# DR_EIB-128_expandedv1_3.net
KiCad netlist of a schematic drawn in EAGLE
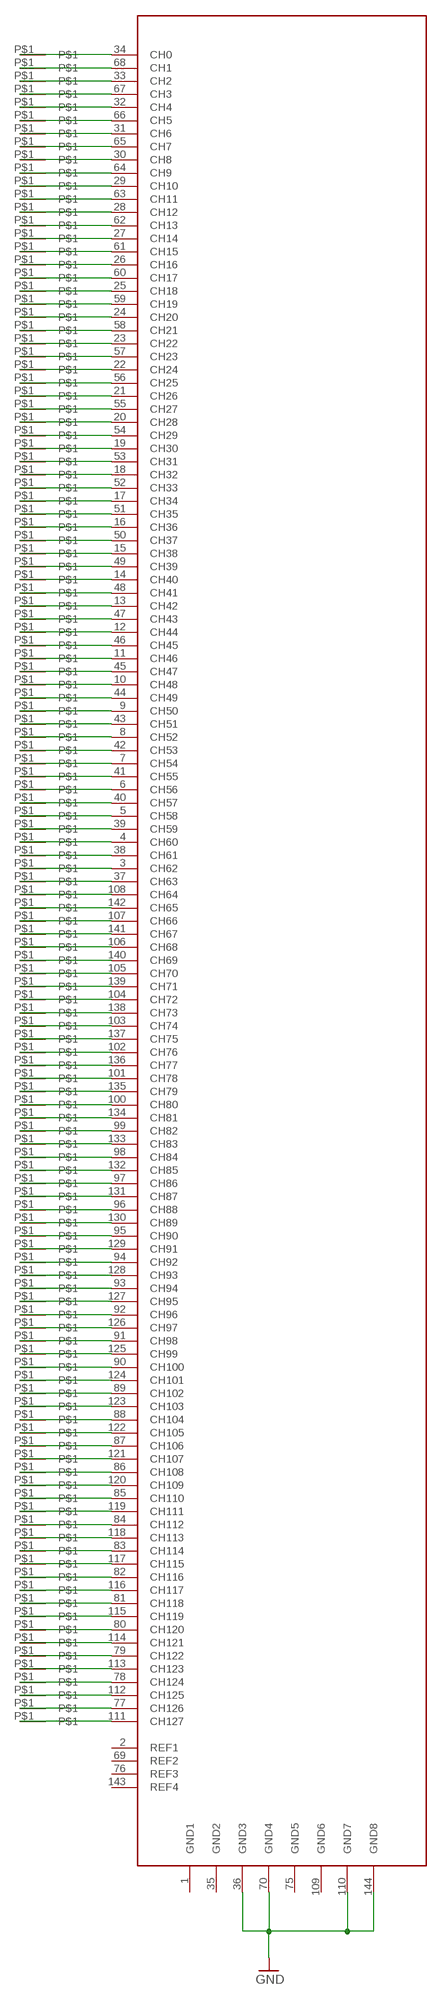
[diagram p0: schematic, sheet 1]

(export (version "E")
  (design (tool "Eeschema 10.0.6"))
  (components
    (comp (ref "H$0")
      (value "TARRAYSHUTTLEHOLE")
      (footprint "eagle-import:TARRAYSHUTTLEHOLE")
      (libsource (lib "eagle-import") (part "TARRAYSHUTTLEHOLE"))
    )
    (comp (ref "H$1")
      (value "TARRAYSHUTTLEHOLE")
      (footprint "eagle-import:TARRAYSHUTTLEHOLE")
      (libsource (lib "eagle-import") (part "TARRAYSHUTTLEHOLE"))
    )
    (comp (ref "H$2")
      (value "TARRAYSHUTTLEHOLE")
      (footprint "eagle-import:TARRAYSHUTTLEHOLE")
      (libsource (lib "eagle-import") (part "TARRAYSHUTTLEHOLE"))
    )
    (comp (ref "H$3")
      (value "TARRAYSHUTTLEHOLE")
      (footprint "eagle-import:TARRAYSHUTTLEHOLE")
      (libsource (lib "eagle-import") (part "TARRAYSHUTTLEHOLE"))
    )
    (comp (ref "H$4")
      (value "TARRAYSHUTTLEHOLE")
      (footprint "eagle-import:TARRAYSHUTTLEHOLE")
      (libsource (lib "eagle-import") (part "TARRAYSHUTTLEHOLE"))
    )
    (comp (ref "H$5")
      (value "TARRAYSHUTTLEHOLE")
      (footprint "eagle-import:TARRAYSHUTTLEHOLE")
      (libsource (lib "eagle-import") (part "TARRAYSHUTTLEHOLE"))
    )
    (comp (ref "H$6")
      (value "TARRAYSHUTTLEHOLE")
      (footprint "eagle-import:TARRAYSHUTTLEHOLE")
      (libsource (lib "eagle-import") (part "TARRAYSHUTTLEHOLE"))
    )
    (comp (ref "H$7")
      (value "TARRAYSHUTTLEHOLE")
      (footprint "eagle-import:TARRAYSHUTTLEHOLE")
      (libsource (lib "eagle-import") (part "TARRAYSHUTTLEHOLE"))
    )
    (comp (ref "H$8")
      (value "TARRAYSHUTTLEHOLE")
      (footprint "eagle-import:TARRAYSHUTTLEHOLE")
      (libsource (lib "eagle-import") (part "TARRAYSHUTTLEHOLE"))
    )
    (comp (ref "H$9")
      (value "TARRAYSHUTTLEHOLE")
      (footprint "eagle-import:TARRAYSHUTTLEHOLE")
      (libsource (lib "eagle-import") (part "TARRAYSHUTTLEHOLE"))
    )
    (comp (ref "H$10")
      (value "TARRAYSHUTTLEHOLE")
      (footprint "eagle-import:TARRAYSHUTTLEHOLE")
      (libsource (lib "eagle-import") (part "TARRAYSHUTTLEHOLE"))
    )
    (comp (ref "H$11")
      (value "TARRAYSHUTTLEHOLE")
      (footprint "eagle-import:TARRAYSHUTTLEHOLE")
      (libsource (lib "eagle-import") (part "TARRAYSHUTTLEHOLE"))
    )
    (comp (ref "H$12")
      (value "TARRAYSHUTTLEHOLE")
      (footprint "eagle-import:TARRAYSHUTTLEHOLE")
      (libsource (lib "eagle-import") (part "TARRAYSHUTTLEHOLE"))
    )
    (comp (ref "H$13")
      (value "TARRAYSHUTTLEHOLE")
      (footprint "eagle-import:TARRAYSHUTTLEHOLE")
      (libsource (lib "eagle-import") (part "TARRAYSHUTTLEHOLE"))
    )
    (comp (ref "H$14")
      (value "TARRAYSHUTTLEHOLE")
      (footprint "eagle-import:TARRAYSHUTTLEHOLE")
      (libsource (lib "eagle-import") (part "TARRAYSHUTTLEHOLE"))
    )
    (comp (ref "H$15")
      (value "TARRAYSHUTTLEHOLE")
      (footprint "eagle-import:TARRAYSHUTTLEHOLE")
      (libsource (lib "eagle-import") (part "TARRAYSHUTTLEHOLE"))
    )
    (comp (ref "H$16")
      (value "TARRAYSHUTTLEHOLE")
      (footprint "eagle-import:TARRAYSHUTTLEHOLE")
      (libsource (lib "eagle-import") (part "TARRAYSHUTTLEHOLE"))
    )
    (comp (ref "H$17")
      (value "TARRAYSHUTTLEHOLE")
      (footprint "eagle-import:TARRAYSHUTTLEHOLE")
      (libsource (lib "eagle-import") (part "TARRAYSHUTTLEHOLE"))
    )
    (comp (ref "H$18")
      (value "TARRAYSHUTTLEHOLE")
      (footprint "eagle-import:TARRAYSHUTTLEHOLE")
      (libsource (lib "eagle-import") (part "TARRAYSHUTTLEHOLE"))
    )
    (comp (ref "H$19")
      (value "TARRAYSHUTTLEHOLE")
      (footprint "eagle-import:TARRAYSHUTTLEHOLE")
      (libsource (lib "eagle-import") (part "TARRAYSHUTTLEHOLE"))
    )
    (comp (ref "H$20")
      (value "TARRAYSHUTTLEHOLE")
      (footprint "eagle-import:TARRAYSHUTTLEHOLE")
      (libsource (lib "eagle-import") (part "TARRAYSHUTTLEHOLE"))
    )
    (comp (ref "H$21")
      (value "TARRAYSHUTTLEHOLE")
      (footprint "eagle-import:TARRAYSHUTTLEHOLE")
      (libsource (lib "eagle-import") (part "TARRAYSHUTTLEHOLE"))
    )
    (comp (ref "H$22")
      (value "TARRAYSHUTTLEHOLE")
      (footprint "eagle-import:TARRAYSHUTTLEHOLE")
      (libsource (lib "eagle-import") (part "TARRAYSHUTTLEHOLE"))
    )
    (comp (ref "H$23")
      (value "TARRAYSHUTTLEHOLE")
      (footprint "eagle-import:TARRAYSHUTTLEHOLE")
      (libsource (lib "eagle-import") (part "TARRAYSHUTTLEHOLE"))
    )
    (comp (ref "H$24")
      (value "TARRAYSHUTTLEHOLE")
      (footprint "eagle-import:TARRAYSHUTTLEHOLE")
      (libsource (lib "eagle-import") (part "TARRAYSHUTTLEHOLE"))
    )
    (comp (ref "H$25")
      (value "TARRAYSHUTTLEHOLE")
      (footprint "eagle-import:TARRAYSHUTTLEHOLE")
      (libsource (lib "eagle-import") (part "TARRAYSHUTTLEHOLE"))
    )
    (comp (ref "H$26")
      (value "TARRAYSHUTTLEHOLE")
      (footprint "eagle-import:TARRAYSHUTTLEHOLE")
      (libsource (lib "eagle-import") (part "TARRAYSHUTTLEHOLE"))
    )
    (comp (ref "H$27")
      (value "TARRAYSHUTTLEHOLE")
      (footprint "eagle-import:TARRAYSHUTTLEHOLE")
      (libsource (lib "eagle-import") (part "TARRAYSHUTTLEHOLE"))
    )
    (comp (ref "H$28")
      (value "TARRAYSHUTTLEHOLE")
      (footprint "eagle-import:TARRAYSHUTTLEHOLE")
      (libsource (lib "eagle-import") (part "TARRAYSHUTTLEHOLE"))
    )
    (comp (ref "H$29")
      (value "TARRAYSHUTTLEHOLE")
      (footprint "eagle-import:TARRAYSHUTTLEHOLE")
      (libsource (lib "eagle-import") (part "TARRAYSHUTTLEHOLE"))
    )
    (comp (ref "H$30")
      (value "TARRAYSHUTTLEHOLE")
      (footprint "eagle-import:TARRAYSHUTTLEHOLE")
      (libsource (lib "eagle-import") (part "TARRAYSHUTTLEHOLE"))
    )
    (comp (ref "H$31")
      (value "TARRAYSHUTTLEHOLE")
      (footprint "eagle-import:TARRAYSHUTTLEHOLE")
      (libsource (lib "eagle-import") (part "TARRAYSHUTTLEHOLE"))
    )
    (comp (ref "H$32")
      (value "TARRAYSHUTTLEHOLE")
      (footprint "eagle-import:TARRAYSHUTTLEHOLE")
      (libsource (lib "eagle-import") (part "TARRAYSHUTTLEHOLE"))
    )
    (comp (ref "H$33")
      (value "TARRAYSHUTTLEHOLE")
      (footprint "eagle-import:TARRAYSHUTTLEHOLE")
      (libsource (lib "eagle-import") (part "TARRAYSHUTTLEHOLE"))
    )
    (comp (ref "H$34")
      (value "TARRAYSHUTTLEHOLE")
      (footprint "eagle-import:TARRAYSHUTTLEHOLE")
      (libsource (lib "eagle-import") (part "TARRAYSHUTTLEHOLE"))
    )
    (comp (ref "H$35")
      (value "TARRAYSHUTTLEHOLE")
      (footprint "eagle-import:TARRAYSHUTTLEHOLE")
      (libsource (lib "eagle-import") (part "TARRAYSHUTTLEHOLE"))
    )
    (comp (ref "H$36")
      (value "TARRAYSHUTTLEHOLE")
      (footprint "eagle-import:TARRAYSHUTTLEHOLE")
      (libsource (lib "eagle-import") (part "TARRAYSHUTTLEHOLE"))
    )
    (comp (ref "H$37")
      (value "TARRAYSHUTTLEHOLE")
      (footprint "eagle-import:TARRAYSHUTTLEHOLE")
      (libsource (lib "eagle-import") (part "TARRAYSHUTTLEHOLE"))
    )
    (comp (ref "H$38")
      (value "TARRAYSHUTTLEHOLE")
      (footprint "eagle-import:TARRAYSHUTTLEHOLE")
      (libsource (lib "eagle-import") (part "TARRAYSHUTTLEHOLE"))
    )
    (comp (ref "H$39")
      (value "TARRAYSHUTTLEHOLE")
      (footprint "eagle-import:TARRAYSHUTTLEHOLE")
      (libsource (lib "eagle-import") (part "TARRAYSHUTTLEHOLE"))
    )
    (comp (ref "H$40")
      (value "TARRAYSHUTTLEHOLE")
      (footprint "eagle-import:TARRAYSHUTTLEHOLE")
      (libsource (lib "eagle-import") (part "TARRAYSHUTTLEHOLE"))
    )
    (comp (ref "H$41")
      (value "TARRAYSHUTTLEHOLE")
      (footprint "eagle-import:TARRAYSHUTTLEHOLE")
      (libsource (lib "eagle-import") (part "TARRAYSHUTTLEHOLE"))
    )
    (comp (ref "H$42")
      (value "TARRAYSHUTTLEHOLE")
      (footprint "eagle-import:TARRAYSHUTTLEHOLE")
      (libsource (lib "eagle-import") (part "TARRAYSHUTTLEHOLE"))
    )
    (comp (ref "H$43")
      (value "TARRAYSHUTTLEHOLE")
      (footprint "eagle-import:TARRAYSHUTTLEHOLE")
      (libsource (lib "eagle-import") (part "TARRAYSHUTTLEHOLE"))
    )
    (comp (ref "H$44")
      (value "TARRAYSHUTTLEHOLE")
      (footprint "eagle-import:TARRAYSHUTTLEHOLE")
      (libsource (lib "eagle-import") (part "TARRAYSHUTTLEHOLE"))
    )
    (comp (ref "H$45")
      (value "TARRAYSHUTTLEHOLE")
      (footprint "eagle-import:TARRAYSHUTTLEHOLE")
      (libsource (lib "eagle-import") (part "TARRAYSHUTTLEHOLE"))
    )
    (comp (ref "H$46")
      (value "TARRAYSHUTTLEHOLE")
      (footprint "eagle-import:TARRAYSHUTTLEHOLE")
      (libsource (lib "eagle-import") (part "TARRAYSHUTTLEHOLE"))
    )
    (comp (ref "H$47")
      (value "TARRAYSHUTTLEHOLE")
      (footprint "eagle-import:TARRAYSHUTTLEHOLE")
      (libsource (lib "eagle-import") (part "TARRAYSHUTTLEHOLE"))
    )
    (comp (ref "H$48")
      (value "TARRAYSHUTTLEHOLE")
      (footprint "eagle-import:TARRAYSHUTTLEHOLE")
      (libsource (lib "eagle-import") (part "TARRAYSHUTTLEHOLE"))
    )
    (comp (ref "H$49")
      (value "TARRAYSHUTTLEHOLE")
      (footprint "eagle-import:TARRAYSHUTTLEHOLE")
      (libsource (lib "eagle-import") (part "TARRAYSHUTTLEHOLE"))
    )
    (comp (ref "H$50")
      (value "TARRAYSHUTTLEHOLE")
      (footprint "eagle-import:TARRAYSHUTTLEHOLE")
      (libsource (lib "eagle-import") (part "TARRAYSHUTTLEHOLE"))
    )
    (comp (ref "H$51")
      (value "TARRAYSHUTTLEHOLE")
      (footprint "eagle-import:TARRAYSHUTTLEHOLE")
      (libsource (lib "eagle-import") (part "TARRAYSHUTTLEHOLE"))
    )
    (comp (ref "H$52")
      (value "TARRAYSHUTTLEHOLE")
      (footprint "eagle-import:TARRAYSHUTTLEHOLE")
      (libsource (lib "eagle-import") (part "TARRAYSHUTTLEHOLE"))
    )
    (comp (ref "H$53")
      (value "TARRAYSHUTTLEHOLE")
      (footprint "eagle-import:TARRAYSHUTTLEHOLE")
      (libsource (lib "eagle-import") (part "TARRAYSHUTTLEHOLE"))
    )
    (comp (ref "H$54")
      (value "TARRAYSHUTTLEHOLE")
      (footprint "eagle-import:TARRAYSHUTTLEHOLE")
      (libsource (lib "eagle-import") (part "TARRAYSHUTTLEHOLE"))
    )
    (comp (ref "H$55")
      (value "TARRAYSHUTTLEHOLE")
      (footprint "eagle-import:TARRAYSHUTTLEHOLE")
      (libsource (lib "eagle-import") (part "TARRAYSHUTTLEHOLE"))
    )
    (comp (ref "H$56")
      (value "TARRAYSHUTTLEHOLE")
      (footprint "eagle-import:TARRAYSHUTTLEHOLE")
      (libsource (lib "eagle-import") (part "TARRAYSHUTTLEHOLE"))
    )
    (comp (ref "H$57")
      (value "TARRAYSHUTTLEHOLE")
      (footprint "eagle-import:TARRAYSHUTTLEHOLE")
      (libsource (lib "eagle-import") (part "TARRAYSHUTTLEHOLE"))
    )
    (comp (ref "H$58")
      (value "TARRAYSHUTTLEHOLE")
      (footprint "eagle-import:TARRAYSHUTTLEHOLE")
      (libsource (lib "eagle-import") (part "TARRAYSHUTTLEHOLE"))
    )
    (comp (ref "H$59")
      (value "TARRAYSHUTTLEHOLE")
      (footprint "eagle-import:TARRAYSHUTTLEHOLE")
      (libsource (lib "eagle-import") (part "TARRAYSHUTTLEHOLE"))
    )
    (comp (ref "H$60")
      (value "TARRAYSHUTTLEHOLE")
      (footprint "eagle-import:TARRAYSHUTTLEHOLE")
      (libsource (lib "eagle-import") (part "TARRAYSHUTTLEHOLE"))
    )
    (comp (ref "H$61")
      (value "TARRAYSHUTTLEHOLE")
      (footprint "eagle-import:TARRAYSHUTTLEHOLE")
      (libsource (lib "eagle-import") (part "TARRAYSHUTTLEHOLE"))
    )
    (comp (ref "H$62")
      (value "TARRAYSHUTTLEHOLE")
      (footprint "eagle-import:TARRAYSHUTTLEHOLE")
      (libsource (lib "eagle-import") (part "TARRAYSHUTTLEHOLE"))
    )
    (comp (ref "H$63")
      (value "TARRAYSHUTTLEHOLE")
      (footprint "eagle-import:TARRAYSHUTTLEHOLE")
      (libsource (lib "eagle-import") (part "TARRAYSHUTTLEHOLE"))
    )
    (comp (ref "H$64")
      (value "TARRAYSHUTTLEHOLE")
      (footprint "eagle-import:TARRAYSHUTTLEHOLE")
      (libsource (lib "eagle-import") (part "TARRAYSHUTTLEHOLE"))
    )
    (comp (ref "H$65")
      (value "TARRAYSHUTTLEHOLE")
      (footprint "eagle-import:TARRAYSHUTTLEHOLE")
      (libsource (lib "eagle-import") (part "TARRAYSHUTTLEHOLE"))
    )
    (comp (ref "H$66")
      (value "TARRAYSHUTTLEHOLE")
      (footprint "eagle-import:TARRAYSHUTTLEHOLE")
      (libsource (lib "eagle-import") (part "TARRAYSHUTTLEHOLE"))
    )
    (comp (ref "H$67")
      (value "TARRAYSHUTTLEHOLE")
      (footprint "eagle-import:TARRAYSHUTTLEHOLE")
      (libsource (lib "eagle-import") (part "TARRAYSHUTTLEHOLE"))
    )
    (comp (ref "H$68")
      (value "TARRAYSHUTTLEHOLE")
      (footprint "eagle-import:TARRAYSHUTTLEHOLE")
      (libsource (lib "eagle-import") (part "TARRAYSHUTTLEHOLE"))
    )
    (comp (ref "H$69")
      (value "TARRAYSHUTTLEHOLE")
      (footprint "eagle-import:TARRAYSHUTTLEHOLE")
      (libsource (lib "eagle-import") (part "TARRAYSHUTTLEHOLE"))
    )
    (comp (ref "H$70")
      (value "TARRAYSHUTTLEHOLE")
      (footprint "eagle-import:TARRAYSHUTTLEHOLE")
      (libsource (lib "eagle-import") (part "TARRAYSHUTTLEHOLE"))
    )
    (comp (ref "H$71")
      (value "TARRAYSHUTTLEHOLE")
      (footprint "eagle-import:TARRAYSHUTTLEHOLE")
      (libsource (lib "eagle-import") (part "TARRAYSHUTTLEHOLE"))
    )
    (comp (ref "H$72")
      (value "TARRAYSHUTTLEHOLE")
      (footprint "eagle-import:TARRAYSHUTTLEHOLE")
      (libsource (lib "eagle-import") (part "TARRAYSHUTTLEHOLE"))
    )
    (comp (ref "H$73")
      (value "TARRAYSHUTTLEHOLE")
      (footprint "eagle-import:TARRAYSHUTTLEHOLE")
      (libsource (lib "eagle-import") (part "TARRAYSHUTTLEHOLE"))
    )
    (comp (ref "H$74")
      (value "TARRAYSHUTTLEHOLE")
      (footprint "eagle-import:TARRAYSHUTTLEHOLE")
      (libsource (lib "eagle-import") (part "TARRAYSHUTTLEHOLE"))
    )
    (comp (ref "H$75")
      (value "TARRAYSHUTTLEHOLE")
      (footprint "eagle-import:TARRAYSHUTTLEHOLE")
      (libsource (lib "eagle-import") (part "TARRAYSHUTTLEHOLE"))
    )
    (comp (ref "H$76")
      (value "TARRAYSHUTTLEHOLE")
      (footprint "eagle-import:TARRAYSHUTTLEHOLE")
      (libsource (lib "eagle-import") (part "TARRAYSHUTTLEHOLE"))
    )
    (comp (ref "H$77")
      (value "TARRAYSHUTTLEHOLE")
      (footprint "eagle-import:TARRAYSHUTTLEHOLE")
      (libsource (lib "eagle-import") (part "TARRAYSHUTTLEHOLE"))
    )
    (comp (ref "H$78")
      (value "TARRAYSHUTTLEHOLE")
      (footprint "eagle-import:TARRAYSHUTTLEHOLE")
      (libsource (lib "eagle-import") (part "TARRAYSHUTTLEHOLE"))
    )
    (comp (ref "H$79")
      (value "TARRAYSHUTTLEHOLE")
      (footprint "eagle-import:TARRAYSHUTTLEHOLE")
      (libsource (lib "eagle-import") (part "TARRAYSHUTTLEHOLE"))
    )
    (comp (ref "H$80")
      (value "TARRAYSHUTTLEHOLE")
      (footprint "eagle-import:TARRAYSHUTTLEHOLE")
      (libsource (lib "eagle-import") (part "TARRAYSHUTTLEHOLE"))
    )
    (comp (ref "H$81")
      (value "TARRAYSHUTTLEHOLE")
      (footprint "eagle-import:TARRAYSHUTTLEHOLE")
      (libsource (lib "eagle-import") (part "TARRAYSHUTTLEHOLE"))
    )
    (comp (ref "H$82")
      (value "TARRAYSHUTTLEHOLE")
      (footprint "eagle-import:TARRAYSHUTTLEHOLE")
      (libsource (lib "eagle-import") (part "TARRAYSHUTTLEHOLE"))
    )
    (comp (ref "H$83")
      (value "TARRAYSHUTTLEHOLE")
      (footprint "eagle-import:TARRAYSHUTTLEHOLE")
      (libsource (lib "eagle-import") (part "TARRAYSHUTTLEHOLE"))
    )
    (comp (ref "H$84")
      (value "TARRAYSHUTTLEHOLE")
      (footprint "eagle-import:TARRAYSHUTTLEHOLE")
      (libsource (lib "eagle-import") (part "TARRAYSHUTTLEHOLE"))
    )
    (comp (ref "H$85")
      (value "TARRAYSHUTTLEHOLE")
      (footprint "eagle-import:TARRAYSHUTTLEHOLE")
      (libsource (lib "eagle-import") (part "TARRAYSHUTTLEHOLE"))
    )
    (comp (ref "H$86")
      (value "TARRAYSHUTTLEHOLE")
      (footprint "eagle-import:TARRAYSHUTTLEHOLE")
      (libsource (lib "eagle-import") (part "TARRAYSHUTTLEHOLE"))
    )
    (comp (ref "H$87")
      (value "TARRAYSHUTTLEHOLE")
      (footprint "eagle-import:TARRAYSHUTTLEHOLE")
      (libsource (lib "eagle-import") (part "TARRAYSHUTTLEHOLE"))
    )
    (comp (ref "H$88")
      (value "TARRAYSHUTTLEHOLE")
      (footprint "eagle-import:TARRAYSHUTTLEHOLE")
      (libsource (lib "eagle-import") (part "TARRAYSHUTTLEHOLE"))
    )
    (comp (ref "H$89")
      (value "TARRAYSHUTTLEHOLE")
      (footprint "eagle-import:TARRAYSHUTTLEHOLE")
      (libsource (lib "eagle-import") (part "TARRAYSHUTTLEHOLE"))
    )
    (comp (ref "H$90")
      (value "TARRAYSHUTTLEHOLE")
      (footprint "eagle-import:TARRAYSHUTTLEHOLE")
      (libsource (lib "eagle-import") (part "TARRAYSHUTTLEHOLE"))
    )
    (comp (ref "H$91")
      (value "TARRAYSHUTTLEHOLE")
      (footprint "eagle-import:TARRAYSHUTTLEHOLE")
      (libsource (lib "eagle-import") (part "TARRAYSHUTTLEHOLE"))
    )
    (comp (ref "H$92")
      (value "TARRAYSHUTTLEHOLE")
      (footprint "eagle-import:TARRAYSHUTTLEHOLE")
      (libsource (lib "eagle-import") (part "TARRAYSHUTTLEHOLE"))
    )
    (comp (ref "H$93")
      (value "TARRAYSHUTTLEHOLE")
      (footprint "eagle-import:TARRAYSHUTTLEHOLE")
      (libsource (lib "eagle-import") (part "TARRAYSHUTTLEHOLE"))
    )
    (comp (ref "H$94")
      (value "TARRAYSHUTTLEHOLE")
      (footprint "eagle-import:TARRAYSHUTTLEHOLE")
      (libsource (lib "eagle-import") (part "TARRAYSHUTTLEHOLE"))
    )
    (comp (ref "H$95")
      (value "TARRAYSHUTTLEHOLE")
      (footprint "eagle-import:TARRAYSHUTTLEHOLE")
      (libsource (lib "eagle-import") (part "TARRAYSHUTTLEHOLE"))
    )
    (comp (ref "H$96")
      (value "TARRAYSHUTTLEHOLE")
      (footprint "eagle-import:TARRAYSHUTTLEHOLE")
      (libsource (lib "eagle-import") (part "TARRAYSHUTTLEHOLE"))
    )
    (comp (ref "H$97")
      (value "TARRAYSHUTTLEHOLE")
      (footprint "eagle-import:TARRAYSHUTTLEHOLE")
      (libsource (lib "eagle-import") (part "TARRAYSHUTTLEHOLE"))
    )
    (comp (ref "H$98")
      (value "TARRAYSHUTTLEHOLE")
      (footprint "eagle-import:TARRAYSHUTTLEHOLE")
      (libsource (lib "eagle-import") (part "TARRAYSHUTTLEHOLE"))
    )
    (comp (ref "H$99")
      (value "TARRAYSHUTTLEHOLE")
      (footprint "eagle-import:TARRAYSHUTTLEHOLE")
      (libsource (lib "eagle-import") (part "TARRAYSHUTTLEHOLE"))
    )
    (comp (ref "H$100")
      (value "TARRAYSHUTTLEHOLE")
      (footprint "eagle-import:TARRAYSHUTTLEHOLE")
      (libsource (lib "eagle-import") (part "TARRAYSHUTTLEHOLE"))
    )
    (comp (ref "H$101")
      (value "TARRAYSHUTTLEHOLE")
      (footprint "eagle-import:TARRAYSHUTTLEHOLE")
      (libsource (lib "eagle-import") (part "TARRAYSHUTTLEHOLE"))
    )
    (comp (ref "H$102")
      (value "TARRAYSHUTTLEHOLE")
      (footprint "eagle-import:TARRAYSHUTTLEHOLE")
      (libsource (lib "eagle-import") (part "TARRAYSHUTTLEHOLE"))
    )
    (comp (ref "H$103")
      (value "TARRAYSHUTTLEHOLE")
      (footprint "eagle-import:TARRAYSHUTTLEHOLE")
      (libsource (lib "eagle-import") (part "TARRAYSHUTTLEHOLE"))
    )
    (comp (ref "H$104")
      (value "TARRAYSHUTTLEHOLE")
      (footprint "eagle-import:TARRAYSHUTTLEHOLE")
      (libsource (lib "eagle-import") (part "TARRAYSHUTTLEHOLE"))
    )
    (comp (ref "H$105")
      (value "TARRAYSHUTTLEHOLE")
      (footprint "eagle-import:TARRAYSHUTTLEHOLE")
      (libsource (lib "eagle-import") (part "TARRAYSHUTTLEHOLE"))
    )
    (comp (ref "H$106")
      (value "TARRAYSHUTTLEHOLE")
      (footprint "eagle-import:TARRAYSHUTTLEHOLE")
      (libsource (lib "eagle-import") (part "TARRAYSHUTTLEHOLE"))
    )
    (comp (ref "H$107")
      (value "TARRAYSHUTTLEHOLE")
      (footprint "eagle-import:TARRAYSHUTTLEHOLE")
      (libsource (lib "eagle-import") (part "TARRAYSHUTTLEHOLE"))
    )
    (comp (ref "H$108")
      (value "TARRAYSHUTTLEHOLE")
      (footprint "eagle-import:TARRAYSHUTTLEHOLE")
      (libsource (lib "eagle-import") (part "TARRAYSHUTTLEHOLE"))
    )
    (comp (ref "H$109")
      (value "TARRAYSHUTTLEHOLE")
      (footprint "eagle-import:TARRAYSHUTTLEHOLE")
      (libsource (lib "eagle-import") (part "TARRAYSHUTTLEHOLE"))
    )
    (comp (ref "H$110")
      (value "TARRAYSHUTTLEHOLE")
      (footprint "eagle-import:TARRAYSHUTTLEHOLE")
      (libsource (lib "eagle-import") (part "TARRAYSHUTTLEHOLE"))
    )
    (comp (ref "H$111")
      (value "TARRAYSHUTTLEHOLE")
      (footprint "eagle-import:TARRAYSHUTTLEHOLE")
      (libsource (lib "eagle-import") (part "TARRAYSHUTTLEHOLE"))
    )
    (comp (ref "H$112")
      (value "TARRAYSHUTTLEHOLE")
      (footprint "eagle-import:TARRAYSHUTTLEHOLE")
      (libsource (lib "eagle-import") (part "TARRAYSHUTTLEHOLE"))
    )
    (comp (ref "H$113")
      (value "TARRAYSHUTTLEHOLE")
      (footprint "eagle-import:TARRAYSHUTTLEHOLE")
      (libsource (lib "eagle-import") (part "TARRAYSHUTTLEHOLE"))
    )
    (comp (ref "H$114")
      (value "TARRAYSHUTTLEHOLE")
      (footprint "eagle-import:TARRAYSHUTTLEHOLE")
      (libsource (lib "eagle-import") (part "TARRAYSHUTTLEHOLE"))
    )
    (comp (ref "H$115")
      (value "TARRAYSHUTTLEHOLE")
      (footprint "eagle-import:TARRAYSHUTTLEHOLE")
      (libsource (lib "eagle-import") (part "TARRAYSHUTTLEHOLE"))
    )
    (comp (ref "H$116")
      (value "TARRAYSHUTTLEHOLE")
      (footprint "eagle-import:TARRAYSHUTTLEHOLE")
      (libsource (lib "eagle-import") (part "TARRAYSHUTTLEHOLE"))
    )
    (comp (ref "H$117")
      (value "TARRAYSHUTTLEHOLE")
      (footprint "eagle-import:TARRAYSHUTTLEHOLE")
      (libsource (lib "eagle-import") (part "TARRAYSHUTTLEHOLE"))
    )
    (comp (ref "H$118")
      (value "TARRAYSHUTTLEHOLE")
      (footprint "eagle-import:TARRAYSHUTTLEHOLE")
      (libsource (lib "eagle-import") (part "TARRAYSHUTTLEHOLE"))
    )
    (comp (ref "H$119")
      (value "TARRAYSHUTTLEHOLE")
      (footprint "eagle-import:TARRAYSHUTTLEHOLE")
      (libsource (lib "eagle-import") (part "TARRAYSHUTTLEHOLE"))
    )
    (comp (ref "H$120")
      (value "TARRAYSHUTTLEHOLE")
      (footprint "eagle-import:TARRAYSHUTTLEHOLE")
      (libsource (lib "eagle-import") (part "TARRAYSHUTTLEHOLE"))
    )
    (comp (ref "H$121")
      (value "TARRAYSHUTTLEHOLE")
      (footprint "eagle-import:TARRAYSHUTTLEHOLE")
      (libsource (lib "eagle-import") (part "TARRAYSHUTTLEHOLE"))
    )
    (comp (ref "H$122")
      (value "TARRAYSHUTTLEHOLE")
      (footprint "eagle-import:TARRAYSHUTTLEHOLE")
      (libsource (lib "eagle-import") (part "TARRAYSHUTTLEHOLE"))
    )
    (comp (ref "H$123")
      (value "TARRAYSHUTTLEHOLE")
      (footprint "eagle-import:TARRAYSHUTTLEHOLE")
      (libsource (lib "eagle-import") (part "TARRAYSHUTTLEHOLE"))
    )
    (comp (ref "H$124")
      (value "TARRAYSHUTTLEHOLE")
      (footprint "eagle-import:TARRAYSHUTTLEHOLE")
      (libsource (lib "eagle-import") (part "TARRAYSHUTTLEHOLE"))
    )
    (comp (ref "H$125")
      (value "TARRAYSHUTTLEHOLE")
      (footprint "eagle-import:TARRAYSHUTTLEHOLE")
      (libsource (lib "eagle-import") (part "TARRAYSHUTTLEHOLE"))
    )
    (comp (ref "H$126")
      (value "TARRAYSHUTTLEHOLE")
      (footprint "eagle-import:TARRAYSHUTTLEHOLE")
      (libsource (lib "eagle-import") (part "TARRAYSHUTTLEHOLE"))
    )
    (comp (ref "H$127")
      (value "TARRAYSHUTTLEHOLE")
      (footprint "eagle-import:TARRAYSHUTTLEHOLE")
      (libsource (lib "eagle-import") (part "TARRAYSHUTTLEHOLE"))
    )
    (comp (ref "U$3")
      (value "128CH-MODULE")
      (footprint "eagle-import:128CH-MODULE")
      (libsource (lib "eagle-import") (part "128CH-MODULE"))
    )
  )
  (nets
    (net (code "1") (name "/GND1") (class "Default")
      (node (ref "U$3") (pin "1") (pinfunction "GND1_1") (pintype "power_in"))
    )
    (net (code "2") (name "/GND2") (class "Default")
      (node (ref "U$3") (pin "35") (pinfunction "GND2_35") (pintype "power_in"))
    )
    (net (code "3") (name "/GND5") (class "Default")
      (node (ref "U$3") (pin "75") (pinfunction "GND5_75") (pintype "power_in"))
    )
    (net (code "4") (name "/GND6") (class "Default")
      (node (ref "U$3") (pin "109") (pinfunction "GND6_109") (pintype "power_in"))
    )
    (net (code "5") (name "GND") (class "Default")
      (node (ref "U$3") (pin "110") (pinfunction "GND7_110") (pintype "power_in"))
      (node (ref "U$3") (pin "144") (pinfunction "GND8_144") (pintype "power_in"))
      (node (ref "U$3") (pin "36") (pinfunction "GND3_36") (pintype "power_in"))
      (node (ref "U$3") (pin "70") (pinfunction "GND4_70") (pintype "power_in"))
    )
    (net (code "6") (name "Net-(U$3-CH0)") (class "Default")
      (node (ref "H$0") (pin "P$1") (pinfunction "P$1_P$1") (pintype "bidirectional"))
      (node (ref "U$3") (pin "34") (pinfunction "CH0_34") (pintype "input"))
    )
    (net (code "7") (name "Net-(U$3-CH1)") (class "Default")
      (node (ref "H$1") (pin "P$1") (pinfunction "P$1_P$1") (pintype "bidirectional"))
      (node (ref "U$3") (pin "68") (pinfunction "CH1_68") (pintype "input"))
    )
    (net (code "8") (name "Net-(U$3-CH2)") (class "Default")
      (node (ref "H$2") (pin "P$1") (pinfunction "P$1_P$1") (pintype "bidirectional"))
      (node (ref "U$3") (pin "33") (pinfunction "CH2_33") (pintype "input"))
    )
    (net (code "9") (name "Net-(U$3-CH3)") (class "Default")
      (node (ref "H$3") (pin "P$1") (pinfunction "P$1_P$1") (pintype "bidirectional"))
      (node (ref "U$3") (pin "67") (pinfunction "CH3_67") (pintype "input"))
    )
    (net (code "10") (name "Net-(U$3-CH4)") (class "Default")
      (node (ref "H$4") (pin "P$1") (pinfunction "P$1_P$1") (pintype "bidirectional"))
      (node (ref "U$3") (pin "32") (pinfunction "CH4_32") (pintype "input"))
    )
    (net (code "11") (name "Net-(U$3-CH5)") (class "Default")
      (node (ref "H$5") (pin "P$1") (pinfunction "P$1_P$1") (pintype "bidirectional"))
      (node (ref "U$3") (pin "66") (pinfunction "CH5_66") (pintype "input"))
    )
    (net (code "12") (name "Net-(U$3-CH6)") (class "Default")
      (node (ref "H$6") (pin "P$1") (pinfunction "P$1_P$1") (pintype "bidirectional"))
      (node (ref "U$3") (pin "31") (pinfunction "CH6_31") (pintype "input"))
    )
    (net (code "13") (name "Net-(U$3-CH7)") (class "Default")
      (node (ref "H$7") (pin "P$1") (pinfunction "P$1_P$1") (pintype "bidirectional"))
      (node (ref "U$3") (pin "65") (pinfunction "CH7_65") (pintype "input"))
    )
    (net (code "14") (name "Net-(U$3-CH8)") (class "Default")
      (node (ref "H$8") (pin "P$1") (pinfunction "P$1_P$1") (pintype "bidirectional"))
      (node (ref "U$3") (pin "30") (pinfunction "CH8_30") (pintype "input"))
    )
    (net (code "15") (name "Net-(U$3-CH9)") (class "Default")
      (node (ref "H$9") (pin "P$1") (pinfunction "P$1_P$1") (pintype "bidirectional"))
      (node (ref "U$3") (pin "64") (pinfunction "CH9_64") (pintype "input"))
    )
    (net (code "16") (name "Net-(U$3-CH10)") (class "Default")
      (node (ref "H$10") (pin "P$1") (pinfunction "P$1_P$1") (pintype "bidirectional"))
      (node (ref "U$3") (pin "29") (pinfunction "CH10_29") (pintype "input"))
    )
    (net (code "17") (name "Net-(U$3-CH11)") (class "Default")
      (node (ref "H$11") (pin "P$1") (pinfunction "P$1_P$1") (pintype "bidirectional"))
      (node (ref "U$3") (pin "63") (pinfunction "CH11_63") (pintype "input"))
    )
    (net (code "18") (name "Net-(U$3-CH12)") (class "Default")
      (node (ref "H$12") (pin "P$1") (pinfunction "P$1_P$1") (pintype "bidirectional"))
      (node (ref "U$3") (pin "28") (pinfunction "CH12_28") (pintype "input"))
    )
    (net (code "19") (name "Net-(U$3-CH13)") (class "Default")
      (node (ref "H$13") (pin "P$1") (pinfunction "P$1_P$1") (pintype "bidirectional"))
      (node (ref "U$3") (pin "62") (pinfunction "CH13_62") (pintype "input"))
    )
    (net (code "20") (name "Net-(U$3-CH14)") (class "Default")
      (node (ref "H$14") (pin "P$1") (pinfunction "P$1_P$1") (pintype "bidirectional"))
      (node (ref "U$3") (pin "27") (pinfunction "CH14_27") (pintype "input"))
    )
    (net (code "21") (name "Net-(U$3-CH15)") (class "Default")
      (node (ref "H$15") (pin "P$1") (pinfunction "P$1_P$1") (pintype "bidirectional"))
      (node (ref "U$3") (pin "61") (pinfunction "CH15_61") (pintype "input"))
    )
    (net (code "22") (name "Net-(U$3-CH16)") (class "Default")
      (node (ref "H$16") (pin "P$1") (pinfunction "P$1_P$1") (pintype "bidirectional"))
      (node (ref "U$3") (pin "26") (pinfunction "CH16_26") (pintype "input"))
    )
    (net (code "23") (name "Net-(U$3-CH17)") (class "Default")
      (node (ref "H$17") (pin "P$1") (pinfunction "P$1_P$1") (pintype "bidirectional"))
      (node (ref "U$3") (pin "60") (pinfunction "CH17_60") (pintype "input"))
    )
    (net (code "24") (name "Net-(U$3-CH18)") (class "Default")
      (node (ref "H$18") (pin "P$1") (pinfunction "P$1_P$1") (pintype "bidirectional"))
      (node (ref "U$3") (pin "25") (pinfunction "CH18_25") (pintype "input"))
    )
    (net (code "25") (name "Net-(U$3-CH19)") (class "Default")
      (node (ref "H$19") (pin "P$1") (pinfunction "P$1_P$1") (pintype "bidirectional"))
      (node (ref "U$3") (pin "59") (pinfunction "CH19_59") (pintype "input"))
    )
    (net (code "26") (name "Net-(U$3-CH20)") (class "Default")
      (node (ref "H$20") (pin "P$1") (pinfunction "P$1_P$1") (pintype "bidirectional"))
      (node (ref "U$3") (pin "24") (pinfunction "CH20_24") (pintype "input"))
    )
    (net (code "27") (name "Net-(U$3-CH21)") (class "Default")
      (node (ref "H$21") (pin "P$1") (pinfunction "P$1_P$1") (pintype "bidirectional"))
      (node (ref "U$3") (pin "58") (pinfunction "CH21_58") (pintype "input"))
    )
    (net (code "28") (name "Net-(U$3-CH22)") (class "Default")
      (node (ref "H$22") (pin "P$1") (pinfunction "P$1_P$1") (pintype "bidirectional"))
      (node (ref "U$3") (pin "23") (pinfunction "CH22_23") (pintype "input"))
    )
    (net (code "29") (name "Net-(U$3-CH23)") (class "Default")
      (node (ref "H$23") (pin "P$1") (pinfunction "P$1_P$1") (pintype "bidirectional"))
      (node (ref "U$3") (pin "57") (pinfunction "CH23_57") (pintype "input"))
    )
    (net (code "30") (name "Net-(U$3-CH24)") (class "Default")
      (node (ref "H$24") (pin "P$1") (pinfunction "P$1_P$1") (pintype "bidirectional"))
      (node (ref "U$3") (pin "22") (pinfunction "CH24_22") (pintype "input"))
    )
    (net (code "31") (name "Net-(U$3-CH25)") (class "Default")
      (node (ref "H$25") (pin "P$1") (pinfunction "P$1_P$1") (pintype "bidirectional"))
      (node (ref "U$3") (pin "56") (pinfunction "CH25_56") (pintype "input"))
    )
    (net (code "32") (name "Net-(U$3-CH26)") (class "Default")
      (node (ref "H$26") (pin "P$1") (pinfunction "P$1_P$1") (pintype "bidirectional"))
      (node (ref "U$3") (pin "21") (pinfunction "CH26_21") (pintype "input"))
    )
    (net (code "33") (name "Net-(U$3-CH27)") (class "Default")
      (node (ref "H$27") (pin "P$1") (pinfunction "P$1_P$1") (pintype "bidirectional"))
      (node (ref "U$3") (pin "55") (pinfunction "CH27_55") (pintype "input"))
    )
    (net (code "34") (name "Net-(U$3-CH28)") (class "Default")
      (node (ref "H$28") (pin "P$1") (pinfunction "P$1_P$1") (pintype "bidirectional"))
      (node (ref "U$3") (pin "20") (pinfunction "CH28_20") (pintype "input"))
    )
    (net (code "35") (name "Net-(U$3-CH29)") (class "Default")
      (node (ref "H$29") (pin "P$1") (pinfunction "P$1_P$1") (pintype "bidirectional"))
      (node (ref "U$3") (pin "54") (pinfunction "CH29_54") (pintype "input"))
    )
    (net (code "36") (name "Net-(U$3-CH30)") (class "Default")
      (node (ref "H$30") (pin "P$1") (pinfunction "P$1_P$1") (pintype "bidirectional"))
      (node (ref "U$3") (pin "19") (pinfunction "CH30_19") (pintype "input"))
    )
    (net (code "37") (name "Net-(U$3-CH31)") (class "Default")
      (node (ref "H$31") (pin "P$1") (pinfunction "P$1_P$1") (pintype "bidirectional"))
      (node (ref "U$3") (pin "53") (pinfunction "CH31_53") (pintype "input"))
    )
    (net (code "38") (name "Net-(U$3-CH32)") (class "Default")
      (node (ref "H$32") (pin "P$1") (pinfunction "P$1_P$1") (pintype "bidirectional"))
      (node (ref "U$3") (pin "18") (pinfunction "CH32_18") (pintype "input"))
    )
    (net (code "39") (name "Net-(U$3-CH33)") (class "Default")
      (node (ref "H$33") (pin "P$1") (pinfunction "P$1_P$1") (pintype "bidirectional"))
      (node (ref "U$3") (pin "52") (pinfunction "CH33_52") (pintype "input"))
    )
    (net (code "40") (name "Net-(U$3-CH34)") (class "Default")
      (node (ref "H$34") (pin "P$1") (pinfunction "P$1_P$1") (pintype "bidirectional"))
      (node (ref "U$3") (pin "17") (pinfunction "CH34_17") (pintype "input"))
    )
    (net (code "41") (name "Net-(U$3-CH35)") (class "Default")
      (node (ref "H$35") (pin "P$1") (pinfunction "P$1_P$1") (pintype "bidirectional"))
      (node (ref "U$3") (pin "51") (pinfunction "CH35_51") (pintype "input"))
    )
    (net (code "42") (name "Net-(U$3-CH36)") (class "Default")
      (node (ref "H$36") (pin "P$1") (pinfunction "P$1_P$1") (pintype "bidirectional"))
      (node (ref "U$3") (pin "16") (pinfunction "CH36_16") (pintype "input"))
    )
    (net (code "43") (name "Net-(U$3-CH37)") (class "Default")
      (node (ref "H$37") (pin "P$1") (pinfunction "P$1_P$1") (pintype "bidirectional"))
      (node (ref "U$3") (pin "50") (pinfunction "CH37_50") (pintype "input"))
    )
    (net (code "44") (name "Net-(U$3-CH38)") (class "Default")
      (node (ref "H$38") (pin "P$1") (pinfunction "P$1_P$1") (pintype "bidirectional"))
      (node (ref "U$3") (pin "15") (pinfunction "CH38_15") (pintype "input"))
    )
    (net (code "45") (name "Net-(U$3-CH39)") (class "Default")
      (node (ref "H$39") (pin "P$1") (pinfunction "P$1_P$1") (pintype "bidirectional"))
      (node (ref "U$3") (pin "49") (pinfunction "CH39_49") (pintype "input"))
    )
    (net (code "46") (name "Net-(U$3-CH40)") (class "Default")
      (node (ref "H$40") (pin "P$1") (pinfunction "P$1_P$1") (pintype "bidirectional"))
      (node (ref "U$3") (pin "14") (pinfunction "CH40_14") (pintype "input"))
    )
    (net (code "47") (name "Net-(U$3-CH41)") (class "Default")
      (node (ref "H$41") (pin "P$1") (pinfunction "P$1_P$1") (pintype "bidirectional"))
      (node (ref "U$3") (pin "48") (pinfunction "CH41_48") (pintype "input"))
    )
    (net (code "48") (name "Net-(U$3-CH42)") (class "Default")
      (node (ref "H$42") (pin "P$1") (pinfunction "P$1_P$1") (pintype "bidirectional"))
      (node (ref "U$3") (pin "13") (pinfunction "CH42_13") (pintype "input"))
    )
    (net (code "49") (name "Net-(U$3-CH43)") (class "Default")
      (node (ref "H$43") (pin "P$1") (pinfunction "P$1_P$1") (pintype "bidirectional"))
      (node (ref "U$3") (pin "47") (pinfunction "CH43_47") (pintype "input"))
    )
    (net (code "50") (name "Net-(U$3-CH44)") (class "Default")
      (node (ref "H$44") (pin "P$1") (pinfunction "P$1_P$1") (pintype "bidirectional"))
      (node (ref "U$3") (pin "12") (pinfunction "CH44_12") (pintype "input"))
    )
    (net (code "51") (name "Net-(U$3-CH45)") (class "Default")
      (node (ref "H$45") (pin "P$1") (pinfunction "P$1_P$1") (pintype "bidirectional"))
      (node (ref "U$3") (pin "46") (pinfunction "CH45_46") (pintype "input"))
    )
    (net (code "52") (name "Net-(U$3-CH46)") (class "Default")
      (node (ref "H$46") (pin "P$1") (pinfunction "P$1_P$1") (pintype "bidirectional"))
      (node (ref "U$3") (pin "11") (pinfunction "CH46_11") (pintype "input"))
    )
    (net (code "53") (name "Net-(U$3-CH47)") (class "Default")
      (node (ref "H$47") (pin "P$1") (pinfunction "P$1_P$1") (pintype "bidirectional"))
      (node (ref "U$3") (pin "45") (pinfunction "CH47_45") (pintype "input"))
    )
    (net (code "54") (name "Net-(U$3-CH48)") (class "Default")
      (node (ref "H$48") (pin "P$1") (pinfunction "P$1_P$1") (pintype "bidirectional"))
      (node (ref "U$3") (pin "10") (pinfunction "CH48_10") (pintype "input"))
    )
    (net (code "55") (name "Net-(U$3-CH49)") (class "Default")
      (node (ref "H$49") (pin "P$1") (pinfunction "P$1_P$1") (pintype "bidirectional"))
      (node (ref "U$3") (pin "44") (pinfunction "CH49_44") (pintype "input"))
    )
    (net (code "56") (name "Net-(U$3-CH50)") (class "Default")
      (node (ref "H$50") (pin "P$1") (pinfunction "P$1_P$1") (pintype "bidirectional"))
      (node (ref "U$3") (pin "9") (pinfunction "CH50_9") (pintype "input"))
    )
    (net (code "57") (name "Net-(U$3-CH51)") (class "Default")
      (node (ref "H$51") (pin "P$1") (pinfunction "P$1_P$1") (pintype "bidirectional"))
      (node (ref "U$3") (pin "43") (pinfunction "CH51_43") (pintype "input"))
    )
    (net (code "58") (name "Net-(U$3-CH52)") (class "Default")
      (node (ref "H$52") (pin "P$1") (pinfunction "P$1_P$1") (pintype "bidirectional"))
      (node (ref "U$3") (pin "8") (pinfunction "CH52_8") (pintype "input"))
    )
    (net (code "59") (name "Net-(U$3-CH53)") (class "Default")
      (node (ref "H$53") (pin "P$1") (pinfunction "P$1_P$1") (pintype "bidirectional"))
      (node (ref "U$3") (pin "42") (pinfunction "CH53_42") (pintype "input"))
    )
    (net (code "60") (name "Net-(U$3-CH54)") (class "Default")
      (node (ref "H$54") (pin "P$1") (pinfunction "P$1_P$1") (pintype "bidirectional"))
      (node (ref "U$3") (pin "7") (pinfunction "CH54_7") (pintype "input"))
    )
    (net (code "61") (name "Net-(U$3-CH55)") (class "Default")
      (node (ref "H$55") (pin "P$1") (pinfunction "P$1_P$1") (pintype "bidirectional"))
      (node (ref "U$3") (pin "41") (pinfunction "CH55_41") (pintype "input"))
    )
    (net (code "62") (name "Net-(U$3-CH56)") (class "Default")
      (node (ref "H$56") (pin "P$1") (pinfunction "P$1_P$1") (pintype "bidirectional"))
      (node (ref "U$3") (pin "6") (pinfunction "CH56_6") (pintype "input"))
    )
    (net (code "63") (name "Net-(U$3-CH57)") (class "Default")
      (node (ref "H$57") (pin "P$1") (pinfunction "P$1_P$1") (pintype "bidirectional"))
      (node (ref "U$3") (pin "40") (pinfunction "CH57_40") (pintype "input"))
    )
    (net (code "64") (name "Net-(U$3-CH58)") (class "Default")
      (node (ref "H$58") (pin "P$1") (pinfunction "P$1_P$1") (pintype "bidirectional"))
      (node (ref "U$3") (pin "5") (pinfunction "CH58_5") (pintype "input"))
    )
    (net (code "65") (name "Net-(U$3-CH59)") (class "Default")
      (node (ref "H$59") (pin "P$1") (pinfunction "P$1_P$1") (pintype "bidirectional"))
      (node (ref "U$3") (pin "39") (pinfunction "CH59_39") (pintype "input"))
    )
    (net (code "66") (name "Net-(U$3-CH60)") (class "Default")
      (node (ref "H$60") (pin "P$1") (pinfunction "P$1_P$1") (pintype "bidirectional"))
      (node (ref "U$3") (pin "4") (pinfunction "CH60_4") (pintype "input"))
    )
    (net (code "67") (name "Net-(U$3-CH61)") (class "Default")
      (node (ref "H$61") (pin "P$1") (pinfunction "P$1_P$1") (pintype "bidirectional"))
      (node (ref "U$3") (pin "38") (pinfunction "CH61_38") (pintype "input"))
    )
    (net (code "68") (name "Net-(U$3-CH62)") (class "Default")
      (node (ref "H$62") (pin "P$1") (pinfunction "P$1_P$1") (pintype "bidirectional"))
      (node (ref "U$3") (pin "3") (pinfunction "CH62_3") (pintype "input"))
    )
    (net (code "69") (name "Net-(U$3-CH63)") (class "Default")
      (node (ref "H$63") (pin "P$1") (pinfunction "P$1_P$1") (pintype "bidirectional"))
      (node (ref "U$3") (pin "37") (pinfunction "CH63_37") (pintype "input"))
    )
    (net (code "70") (name "Net-(U$3-CH64)") (class "Default")
      (node (ref "H$64") (pin "P$1") (pinfunction "P$1_P$1") (pintype "bidirectional"))
      (node (ref "U$3") (pin "108") (pinfunction "CH64_108") (pintype "input"))
    )
    (net (code "71") (name "Net-(U$3-CH65)") (class "Default")
      (node (ref "H$65") (pin "P$1") (pinfunction "P$1_P$1") (pintype "bidirectional"))
      (node (ref "U$3") (pin "142") (pinfunction "CH65_142") (pintype "input"))
    )
    (net (code "72") (name "Net-(U$3-CH66)") (class "Default")
      (node (ref "H$66") (pin "P$1") (pinfunction "P$1_P$1") (pintype "bidirectional"))
      (node (ref "U$3") (pin "107") (pinfunction "CH66_107") (pintype "input"))
    )
    (net (code "73") (name "Net-(U$3-CH67)") (class "Default")
      (node (ref "H$67") (pin "P$1") (pinfunction "P$1_P$1") (pintype "bidirectional"))
      (node (ref "U$3") (pin "141") (pinfunction "CH67_141") (pintype "input"))
    )
    (net (code "74") (name "Net-(U$3-CH68)") (class "Default")
      (node (ref "H$68") (pin "P$1") (pinfunction "P$1_P$1") (pintype "bidirectional"))
      (node (ref "U$3") (pin "106") (pinfunction "CH68_106") (pintype "input"))
    )
    (net (code "75") (name "Net-(U$3-CH69)") (class "Default")
      (node (ref "H$69") (pin "P$1") (pinfunction "P$1_P$1") (pintype "bidirectional"))
      (node (ref "U$3") (pin "140") (pinfunction "CH69_140") (pintype "input"))
    )
    (net (code "76") (name "Net-(U$3-CH70)") (class "Default")
      (node (ref "H$70") (pin "P$1") (pinfunction "P$1_P$1") (pintype "bidirectional"))
      (node (ref "U$3") (pin "105") (pinfunction "CH70_105") (pintype "input"))
    )
    (net (code "77") (name "Net-(U$3-CH71)") (class "Default")
      (node (ref "H$71") (pin "P$1") (pinfunction "P$1_P$1") (pintype "bidirectional"))
      (node (ref "U$3") (pin "139") (pinfunction "CH71_139") (pintype "input"))
    )
    (net (code "78") (name "Net-(U$3-CH72)") (class "Default")
      (node (ref "H$72") (pin "P$1") (pinfunction "P$1_P$1") (pintype "bidirectional"))
      (node (ref "U$3") (pin "104") (pinfunction "CH72_104") (pintype "input"))
    )
    (net (code "79") (name "Net-(U$3-CH73)") (class "Default")
      (node (ref "H$73") (pin "P$1") (pinfunction "P$1_P$1") (pintype "bidirectional"))
      (node (ref "U$3") (pin "138") (pinfunction "CH73_138") (pintype "input"))
    )
    (net (code "80") (name "Net-(U$3-CH74)") (class "Default")
      (node (ref "H$74") (pin "P$1") (pinfunction "P$1_P$1") (pintype "bidirectional"))
      (node (ref "U$3") (pin "103") (pinfunction "CH74_103") (pintype "input"))
    )
    (net (code "81") (name "Net-(U$3-CH75)") (class "Default")
      (node (ref "H$75") (pin "P$1") (pinfunction "P$1_P$1") (pintype "bidirectional"))
      (node (ref "U$3") (pin "137") (pinfunction "CH75_137") (pintype "input"))
    )
    (net (code "82") (name "Net-(U$3-CH76)") (class "Default")
      (node (ref "H$76") (pin "P$1") (pinfunction "P$1_P$1") (pintype "bidirectional"))
      (node (ref "U$3") (pin "102") (pinfunction "CH76_102") (pintype "input"))
    )
    (net (code "83") (name "Net-(U$3-CH77)") (class "Default")
      (node (ref "H$77") (pin "P$1") (pinfunction "P$1_P$1") (pintype "bidirectional"))
      (node (ref "U$3") (pin "136") (pinfunction "CH77_136") (pintype "input"))
    )
    (net (code "84") (name "Net-(U$3-CH78)") (class "Default")
      (node (ref "H$78") (pin "P$1") (pinfunction "P$1_P$1") (pintype "bidirectional"))
      (node (ref "U$3") (pin "101") (pinfunction "CH78_101") (pintype "input"))
    )
    (net (code "85") (name "Net-(U$3-CH79)") (class "Default")
      (node (ref "H$79") (pin "P$1") (pinfunction "P$1_P$1") (pintype "bidirectional"))
      (node (ref "U$3") (pin "135") (pinfunction "CH79_135") (pintype "input"))
    )
    (net (code "86") (name "Net-(U$3-CH80)") (class "Default")
      (node (ref "H$80") (pin "P$1") (pinfunction "P$1_P$1") (pintype "bidirectional"))
      (node (ref "U$3") (pin "100") (pinfunction "CH80_100") (pintype "input"))
    )
    (net (code "87") (name "Net-(U$3-CH81)") (class "Default")
      (node (ref "H$81") (pin "P$1") (pinfunction "P$1_P$1") (pintype "bidirectional"))
      (node (ref "U$3") (pin "134") (pinfunction "CH81_134") (pintype "input"))
    )
    (net (code "88") (name "Net-(U$3-CH82)") (class "Default")
      (node (ref "H$82") (pin "P$1") (pinfunction "P$1_P$1") (pintype "bidirectional"))
      (node (ref "U$3") (pin "99") (pinfunction "CH82_99") (pintype "input"))
    )
    (net (code "89") (name "Net-(U$3-CH83)") (class "Default")
      (node (ref "H$83") (pin "P$1") (pinfunction "P$1_P$1") (pintype "bidirectional"))
      (node (ref "U$3") (pin "133") (pinfunction "CH83_133") (pintype "input"))
    )
    (net (code "90") (name "Net-(U$3-CH84)") (class "Default")
      (node (ref "H$84") (pin "P$1") (pinfunction "P$1_P$1") (pintype "bidirectional"))
      (node (ref "U$3") (pin "98") (pinfunction "CH84_98") (pintype "input"))
    )
    (net (code "91") (name "Net-(U$3-CH85)") (class "Default")
      (node (ref "H$85") (pin "P$1") (pinfunction "P$1_P$1") (pintype "bidirectional"))
      (node (ref "U$3") (pin "132") (pinfunction "CH85_132") (pintype "input"))
    )
    (net (code "92") (name "Net-(U$3-CH86)") (class "Default")
      (node (ref "H$86") (pin "P$1") (pinfunction "P$1_P$1") (pintype "bidirectional"))
      (node (ref "U$3") (pin "97") (pinfunction "CH86_97") (pintype "input"))
    )
    (net (code "93") (name "Net-(U$3-CH87)") (class "Default")
      (node (ref "H$87") (pin "P$1") (pinfunction "P$1_P$1") (pintype "bidirectional"))
      (node (ref "U$3") (pin "131") (pinfunction "CH87_131") (pintype "input"))
    )
    (net (code "94") (name "Net-(U$3-CH88)") (class "Default")
      (node (ref "H$88") (pin "P$1") (pinfunction "P$1_P$1") (pintype "bidirectional"))
      (node (ref "U$3") (pin "96") (pinfunction "CH88_96") (pintype "input"))
    )
    (net (code "95") (name "Net-(U$3-CH89)") (class "Default")
      (node (ref "H$89") (pin "P$1") (pinfunction "P$1_P$1") (pintype "bidirectional"))
      (node (ref "U$3") (pin "130") (pinfunction "CH89_130") (pintype "input"))
    )
    (net (code "96") (name "Net-(U$3-CH90)") (class "Default")
      (node (ref "H$90") (pin "P$1") (pinfunction "P$1_P$1") (pintype "bidirectional"))
      (node (ref "U$3") (pin "95") (pinfunction "CH90_95") (pintype "input"))
    )
    (net (code "97") (name "Net-(U$3-CH91)") (class "Default")
      (node (ref "H$91") (pin "P$1") (pinfunction "P$1_P$1") (pintype "bidirectional"))
      (node (ref "U$3") (pin "129") (pinfunction "CH91_129") (pintype "input"))
    )
    (net (code "98") (name "Net-(U$3-CH92)") (class "Default")
      (node (ref "H$92") (pin "P$1") (pinfunction "P$1_P$1") (pintype "bidirectional"))
      (node (ref "U$3") (pin "94") (pinfunction "CH92_94") (pintype "input"))
    )
    (net (code "99") (name "Net-(U$3-CH93)") (class "Default")
      (node (ref "H$93") (pin "P$1") (pinfunction "P$1_P$1") (pintype "bidirectional"))
      (node (ref "U$3") (pin "128") (pinfunction "CH93_128") (pintype "input"))
    )
    (net (code "100") (name "Net-(U$3-CH94)") (class "Default")
      (node (ref "H$94") (pin "P$1") (pinfunction "P$1_P$1") (pintype "bidirectional"))
      (node (ref "U$3") (pin "93") (pinfunction "CH94_93") (pintype "input"))
    )
    (net (code "101") (name "Net-(U$3-CH95)") (class "Default")
      (node (ref "H$95") (pin "P$1") (pinfunction "P$1_P$1") (pintype "bidirectional"))
      (node (ref "U$3") (pin "127") (pinfunction "CH95_127") (pintype "input"))
    )
    (net (code "102") (name "Net-(U$3-CH96)") (class "Default")
      (node (ref "H$96") (pin "P$1") (pinfunction "P$1_P$1") (pintype "bidirectional"))
      (node (ref "U$3") (pin "92") (pinfunction "CH96_92") (pintype "input"))
    )
    (net (code "103") (name "Net-(U$3-CH97)") (class "Default")
      (node (ref "H$97") (pin "P$1") (pinfunction "P$1_P$1") (pintype "bidirectional"))
      (node (ref "U$3") (pin "126") (pinfunction "CH97_126") (pintype "input"))
    )
    (net (code "104") (name "Net-(U$3-CH98)") (class "Default")
      (node (ref "H$98") (pin "P$1") (pinfunction "P$1_P$1") (pintype "bidirectional"))
      (node (ref "U$3") (pin "91") (pinfunction "CH98_91") (pintype "input"))
    )
    (net (code "105") (name "Net-(U$3-CH99)") (class "Default")
      (node (ref "H$99") (pin "P$1") (pinfunction "P$1_P$1") (pintype "bidirectional"))
      (node (ref "U$3") (pin "125") (pinfunction "CH99_125") (pintype "input"))
    )
    (net (code "106") (name "Net-(U$3-CH100)") (class "Default")
      (node (ref "H$100") (pin "P$1") (pinfunction "P$1_P$1") (pintype "bidirectional"))
      (node (ref "U$3") (pin "90") (pinfunction "CH100_90") (pintype "input"))
    )
    (net (code "107") (name "Net-(U$3-CH101)") (class "Default")
      (node (ref "H$101") (pin "P$1") (pinfunction "P$1_P$1") (pintype "bidirectional"))
      (node (ref "U$3") (pin "124") (pinfunction "CH101_124") (pintype "input"))
    )
    (net (code "108") (name "Net-(U$3-CH102)") (class "Default")
      (node (ref "H$102") (pin "P$1") (pinfunction "P$1_P$1") (pintype "bidirectional"))
      (node (ref "U$3") (pin "89") (pinfunction "CH102_89") (pintype "input"))
    )
    (net (code "109") (name "Net-(U$3-CH103)") (class "Default")
      (node (ref "H$103") (pin "P$1") (pinfunction "P$1_P$1") (pintype "bidirectional"))
      (node (ref "U$3") (pin "123") (pinfunction "CH103_123") (pintype "input"))
    )
    (net (code "110") (name "Net-(U$3-CH104)") (class "Default")
      (node (ref "H$104") (pin "P$1") (pinfunction "P$1_P$1") (pintype "bidirectional"))
      (node (ref "U$3") (pin "88") (pinfunction "CH104_88") (pintype "input"))
    )
    (net (code "111") (name "Net-(U$3-CH105)") (class "Default")
      (node (ref "H$105") (pin "P$1") (pinfunction "P$1_P$1") (pintype "bidirectional"))
      (node (ref "U$3") (pin "122") (pinfunction "CH105_122") (pintype "input"))
    )
    (net (code "112") (name "Net-(U$3-CH106)") (class "Default")
      (node (ref "H$106") (pin "P$1") (pinfunction "P$1_P$1") (pintype "bidirectional"))
      (node (ref "U$3") (pin "87") (pinfunction "CH106_87") (pintype "input"))
    )
    (net (code "113") (name "Net-(U$3-CH107)") (class "Default")
      (node (ref "H$107") (pin "P$1") (pinfunction "P$1_P$1") (pintype "bidirectional"))
      (node (ref "U$3") (pin "121") (pinfunction "CH107_121") (pintype "input"))
    )
    (net (code "114") (name "Net-(U$3-CH108)") (class "Default")
      (node (ref "H$108") (pin "P$1") (pinfunction "P$1_P$1") (pintype "bidirectional"))
      (node (ref "U$3") (pin "86") (pinfunction "CH108_86") (pintype "input"))
    )
    (net (code "115") (name "Net-(U$3-CH109)") (class "Default")
      (node (ref "H$109") (pin "P$1") (pinfunction "P$1_P$1") (pintype "bidirectional"))
      (node (ref "U$3") (pin "120") (pinfunction "CH109_120") (pintype "input"))
    )
    (net (code "116") (name "Net-(U$3-CH110)") (class "Default")
      (node (ref "H$110") (pin "P$1") (pinfunction "P$1_P$1") (pintype "bidirectional"))
      (node (ref "U$3") (pin "85") (pinfunction "CH110_85") (pintype "input"))
    )
    (net (code "117") (name "Net-(U$3-CH111)") (class "Default")
      (node (ref "H$111") (pin "P$1") (pinfunction "P$1_P$1") (pintype "bidirectional"))
      (node (ref "U$3") (pin "119") (pinfunction "CH111_119") (pintype "input"))
    )
    (net (code "118") (name "Net-(U$3-CH112)") (class "Default")
      (node (ref "H$112") (pin "P$1") (pinfunction "P$1_P$1") (pintype "bidirectional"))
      (node (ref "U$3") (pin "84") (pinfunction "CH112_84") (pintype "input"))
    )
    (net (code "119") (name "Net-(U$3-CH113)") (class "Default")
      (node (ref "H$113") (pin "P$1") (pinfunction "P$1_P$1") (pintype "bidirectional"))
      (node (ref "U$3") (pin "118") (pinfunction "CH113_118") (pintype "input"))
    )
    (net (code "120") (name "Net-(U$3-CH114)") (class "Default")
      (node (ref "H$114") (pin "P$1") (pinfunction "P$1_P$1") (pintype "bidirectional"))
      (node (ref "U$3") (pin "83") (pinfunction "CH114_83") (pintype "input"))
    )
    (net (code "121") (name "Net-(U$3-CH115)") (class "Default")
      (node (ref "H$115") (pin "P$1") (pinfunction "P$1_P$1") (pintype "bidirectional"))
      (node (ref "U$3") (pin "117") (pinfunction "CH115_117") (pintype "input"))
    )
    (net (code "122") (name "Net-(U$3-CH116)") (class "Default")
      (node (ref "H$116") (pin "P$1") (pinfunction "P$1_P$1") (pintype "bidirectional"))
      (node (ref "U$3") (pin "82") (pinfunction "CH116_82") (pintype "input"))
    )
    (net (code "123") (name "Net-(U$3-CH117)") (class "Default")
      (node (ref "H$117") (pin "P$1") (pinfunction "P$1_P$1") (pintype "bidirectional"))
      (node (ref "U$3") (pin "116") (pinfunction "CH117_116") (pintype "input"))
    )
    (net (code "124") (name "Net-(U$3-CH118)") (class "Default")
      (node (ref "H$118") (pin "P$1") (pinfunction "P$1_P$1") (pintype "bidirectional"))
      (node (ref "U$3") (pin "81") (pinfunction "CH118_81") (pintype "input"))
    )
    (net (code "125") (name "Net-(U$3-CH119)") (class "Default")
      (node (ref "H$119") (pin "P$1") (pinfunction "P$1_P$1") (pintype "bidirectional"))
      (node (ref "U$3") (pin "115") (pinfunction "CH119_115") (pintype "input"))
    )
    (net (code "126") (name "Net-(U$3-CH120)") (class "Default")
      (node (ref "H$120") (pin "P$1") (pinfunction "P$1_P$1") (pintype "bidirectional"))
      (node (ref "U$3") (pin "80") (pinfunction "CH120_80") (pintype "input"))
    )
    (net (code "127") (name "Net-(U$3-CH121)") (class "Default")
      (node (ref "H$121") (pin "P$1") (pinfunction "P$1_P$1") (pintype "bidirectional"))
      (node (ref "U$3") (pin "114") (pinfunction "CH121_114") (pintype "input"))
    )
    (net (code "128") (name "Net-(U$3-CH122)") (class "Default")
      (node (ref "H$122") (pin "P$1") (pinfunction "P$1_P$1") (pintype "bidirectional"))
      (node (ref "U$3") (pin "79") (pinfunction "CH122_79") (pintype "input"))
    )
    (net (code "129") (name "Net-(U$3-CH123)") (class "Default")
      (node (ref "H$123") (pin "P$1") (pinfunction "P$1_P$1") (pintype "bidirectional"))
      (node (ref "U$3") (pin "113") (pinfunction "CH123_113") (pintype "input"))
    )
    (net (code "130") (name "Net-(U$3-CH124)") (class "Default")
      (node (ref "H$124") (pin "P$1") (pinfunction "P$1_P$1") (pintype "bidirectional"))
      (node (ref "U$3") (pin "78") (pinfunction "CH124_78") (pintype "input"))
    )
    (net (code "131") (name "Net-(U$3-CH125)") (class "Default")
      (node (ref "H$125") (pin "P$1") (pinfunction "P$1_P$1") (pintype "bidirectional"))
      (node (ref "U$3") (pin "112") (pinfunction "CH125_112") (pintype "input"))
    )
    (net (code "132") (name "Net-(U$3-CH126)") (class "Default")
      (node (ref "H$126") (pin "P$1") (pinfunction "P$1_P$1") (pintype "bidirectional"))
      (node (ref "U$3") (pin "77") (pinfunction "CH126_77") (pintype "input"))
    )
    (net (code "133") (name "Net-(U$3-CH127)") (class "Default")
      (node (ref "H$127") (pin "P$1") (pinfunction "P$1_P$1") (pintype "bidirectional"))
      (node (ref "U$3") (pin "111") (pinfunction "CH127_111") (pintype "input"))
    )
    (net (code "134") (name "unconnected-(U$3-REF1-Pad2)") (class "Default")
      (node (ref "U$3") (pin "2") (pinfunction "REF1_2") (pintype "input"))
    )
    (net (code "135") (name "unconnected-(U$3-REF2-Pad69)") (class "Default")
      (node (ref "U$3") (pin "69") (pinfunction "REF2_69") (pintype "input"))
    )
    (net (code "136") (name "unconnected-(U$3-REF3-Pad76)") (class "Default")
      (node (ref "U$3") (pin "76") (pinfunction "REF3_76") (pintype "input"))
    )
    (net (code "137") (name "unconnected-(U$3-REF4-Pad143)") (class "Default")
      (node (ref "U$3") (pin "143") (pinfunction "REF4_143") (pintype "input"))
    )
  )
)
